# terraco_verde_pcb_impressa.net
KiCad netlist of a schematic drawn in EAGLE
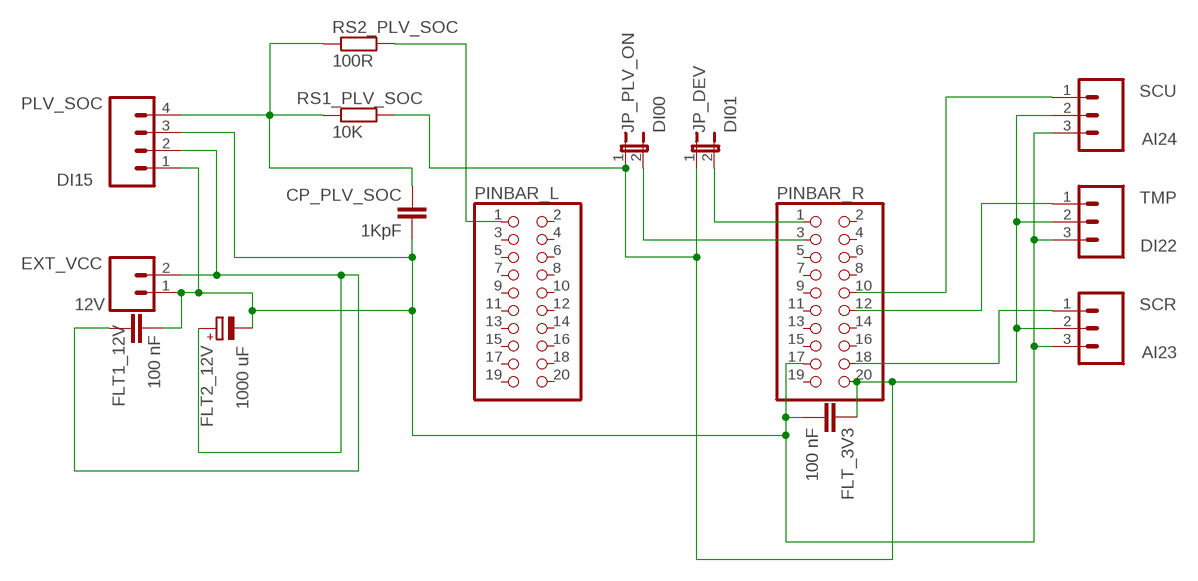
[diagram p0: schematic, sheet 1]

(export (version "E")
  (design (tool "Eeschema 10.0.6"))
  (components
    (comp (ref "CP_PLV_SOC")
      (value "1KpF")
      (footprint "eagle-import:C025-024X044")
      (libsource (lib "eagle-import") (part "C-EU025-024X044"))
    )
    (comp (ref "EXT_VCC")
      (value "12V")
      (footprint "eagle-import:02P")
      (libsource (lib "eagle-import") (part "M02"))
    )
    (comp (ref "FLT1_12V")
      (value "100 nF")
      (footprint "eagle-import:C025-024X044")
      (libsource (lib "eagle-import") (part "C-EU025-024X044"))
    )
    (comp (ref "FLT2_12V")
      (value "1000 uF")
      (footprint "eagle-import:E5-5")
      (libsource (lib "eagle-import") (part "CPOL-EUE5-5"))
    )
    (comp (ref "FLT_3V3")
      (value "100 nF")
      (footprint "eagle-import:C025-024X044")
      (libsource (lib "eagle-import") (part "C-EU025-024X044"))
    )
    (comp (ref "JP_DEV")
      (value "DI01")
      (footprint "eagle-import:JP1")
      (libsource (lib "eagle-import") (part "JP1E"))
    )
    (comp (ref "JP_PLV_ON")
      (value "DI00")
      (footprint "eagle-import:JP1")
      (libsource (lib "eagle-import") (part "JP1E"))
    )
    (comp (ref "PINBAR_L")
      (value "0")
      (footprint "eagle-import:2X10")
      (libsource (lib "eagle-import") (part "PINHD-2X10"))
    )
    (comp (ref "PINBAR_R")
      (value "1")
      (footprint "eagle-import:2X10")
      (libsource (lib "eagle-import") (part "PINHD-2X10"))
    )
    (comp (ref "PLV_SOC")
      (value "DI15")
      (footprint "eagle-import:04P")
      (libsource (lib "eagle-import") (part "M04"))
    )
    (comp (ref "RS1_PLV_SOC")
      (value "10K")
      (footprint "eagle-import:0207_7")
      (libsource (lib "eagle-import") (part "R-EU_0207/7"))
    )
    (comp (ref "RS2_PLV_SOC")
      (value "100R")
      (footprint "eagle-import:0207_7")
      (libsource (lib "eagle-import") (part "R-EU_0207/7"))
    )
    (comp (ref "SCR")
      (value "AI23")
      (footprint "eagle-import:03P")
      (libsource (lib "eagle-import") (part "M03"))
    )
    (comp (ref "SCU")
      (value "AI24")
      (footprint "eagle-import:03P")
      (libsource (lib "eagle-import") (part "M03"))
    )
    (comp (ref "TMP")
      (value "DI22")
      (footprint "eagle-import:03P")
      (libsource (lib "eagle-import") (part "M03"))
    )
  )
  (nets
    (net (code "1") (name "Net-(CP_PLV_SOC-Pad1)") (class "Default")
      (node (ref "CP_PLV_SOC") (pin "1") (pinfunction "1_1") (pintype "passive"))
      (node (ref "EXT_VCC") (pin "1") (pinfunction "1_1") (pintype "passive"))
      (node (ref "FLT1_12V") (pin "2") (pinfunction "2_2") (pintype "passive"))
      (node (ref "FLT2_12V") (pin "-") (pinfunction "-_-") (pintype "passive"))
      (node (ref "FLT_3V3") (pin "2") (pinfunction "2_2") (pintype "passive"))
      (node (ref "PINBAR_R") (pin "17") (pinfunction "17_17") (pintype "passive"))
      (node (ref "PLV_SOC") (pin "1") (pinfunction "1_1") (pintype "passive"))
      (node (ref "PLV_SOC") (pin "3") (pinfunction "3_3") (pintype "passive"))
      (node (ref "SCR") (pin "3") (pinfunction "3_3") (pintype "passive"))
      (node (ref "SCU") (pin "3") (pinfunction "3_3") (pintype "passive"))
      (node (ref "TMP") (pin "3") (pinfunction "3_3") (pintype "passive"))
    )
    (net (code "2") (name "Net-(CP_PLV_SOC-Pad2)") (class "Default")
      (node (ref "CP_PLV_SOC") (pin "2") (pinfunction "2_2") (pintype "passive"))
      (node (ref "PLV_SOC") (pin "4") (pinfunction "4_4") (pintype "passive"))
      (node (ref "RS1_PLV_SOC") (pin "1") (pinfunction "1_1") (pintype "passive"))
      (node (ref "RS2_PLV_SOC") (pin "1") (pinfunction "1_1") (pintype "passive"))
    )
    (net (code "3") (name "Net-(EXT_VCC-Pad2)") (class "Default")
      (node (ref "EXT_VCC") (pin "2") (pinfunction "2_2") (pintype "passive"))
      (node (ref "FLT1_12V") (pin "1") (pinfunction "1_1") (pintype "passive"))
      (node (ref "FLT2_12V") (pin "+") (pinfunction "+_+") (pintype "passive"))
      (node (ref "PLV_SOC") (pin "2") (pinfunction "2_2") (pintype "passive"))
    )
    (net (code "4") (name "Net-(FLT_3V3-Pad1)") (class "Default")
      (node (ref "FLT_3V3") (pin "1") (pinfunction "1_1") (pintype "passive"))
      (node (ref "JP_DEV") (pin "1") (pinfunction "1_1") (pintype "passive"))
      (node (ref "JP_PLV_ON") (pin "1") (pinfunction "1_1") (pintype "passive"))
      (node (ref "PINBAR_R") (pin "20") (pinfunction "20_20") (pintype "passive"))
      (node (ref "RS1_PLV_SOC") (pin "2") (pinfunction "2_2") (pintype "passive"))
      (node (ref "SCR") (pin "2") (pinfunction "2_2") (pintype "passive"))
      (node (ref "SCU") (pin "2") (pinfunction "2_2") (pintype "passive"))
      (node (ref "TMP") (pin "2") (pinfunction "2_2") (pintype "passive"))
    )
    (net (code "5") (name "Net-(JP_DEV-Pad2)") (class "Default")
      (node (ref "JP_DEV") (pin "2") (pinfunction "2_2") (pintype "passive"))
      (node (ref "PINBAR_R") (pin "1") (pinfunction "1_1") (pintype "passive"))
    )
    (net (code "6") (name "Net-(JP_PLV_ON-Pad2)") (class "Default")
      (node (ref "JP_PLV_ON") (pin "2") (pinfunction "2_2") (pintype "passive"))
      (node (ref "PINBAR_R") (pin "3") (pinfunction "3_3") (pintype "passive"))
    )
    (net (code "7") (name "Net-(PINBAR_L-Pad1)") (class "Default")
      (node (ref "PINBAR_L") (pin "1") (pinfunction "1_1") (pintype "passive"))
      (node (ref "RS2_PLV_SOC") (pin "2") (pinfunction "2_2") (pintype "passive"))
    )
    (net (code "8") (name "Net-(PINBAR_R-Pad10)") (class "Default")
      (node (ref "PINBAR_R") (pin "10") (pinfunction "10_10") (pintype "passive"))
      (node (ref "SCU") (pin "1") (pinfunction "1_1") (pintype "passive"))
    )
    (net (code "9") (name "Net-(PINBAR_R-Pad12)") (class "Default")
      (node (ref "PINBAR_R") (pin "12") (pinfunction "12_12") (pintype "passive"))
      (node (ref "TMP") (pin "1") (pinfunction "1_1") (pintype "passive"))
    )
    (net (code "10") (name "Net-(PINBAR_R-Pad18)") (class "Default")
      (node (ref "PINBAR_R") (pin "18") (pinfunction "18_18") (pintype "passive"))
      (node (ref "SCR") (pin "1") (pinfunction "1_1") (pintype "passive"))
    )
    (net (code "11") (name "unconnected-(PINBAR_L-Pad2)") (class "Default")
      (node (ref "PINBAR_L") (pin "2") (pinfunction "2_2") (pintype "passive"))
    )
    (net (code "12") (name "unconnected-(PINBAR_L-Pad3)") (class "Default")
      (node (ref "PINBAR_L") (pin "3") (pinfunction "3_3") (pintype "passive"))
    )
    (net (code "13") (name "unconnected-(PINBAR_L-Pad4)") (class "Default")
      (node (ref "PINBAR_L") (pin "4") (pinfunction "4_4") (pintype "passive"))
    )
    (net (code "14") (name "unconnected-(PINBAR_L-Pad5)") (class "Default")
      (node (ref "PINBAR_L") (pin "5") (pinfunction "5_5") (pintype "passive"))
    )
    (net (code "15") (name "unconnected-(PINBAR_L-Pad6)") (class "Default")
      (node (ref "PINBAR_L") (pin "6") (pinfunction "6_6") (pintype "passive"))
    )
    (net (code "16") (name "unconnected-(PINBAR_L-Pad7)") (class "Default")
      (node (ref "PINBAR_L") (pin "7") (pinfunction "7_7") (pintype "passive"))
    )
    (net (code "17") (name "unconnected-(PINBAR_L-Pad8)") (class "Default")
      (node (ref "PINBAR_L") (pin "8") (pinfunction "8_8") (pintype "passive"))
    )
    (net (code "18") (name "unconnected-(PINBAR_L-Pad9)") (class "Default")
      (node (ref "PINBAR_L") (pin "9") (pinfunction "9_9") (pintype "passive"))
    )
    (net (code "19") (name "unconnected-(PINBAR_L-Pad10)") (class "Default")
      (node (ref "PINBAR_L") (pin "10") (pinfunction "10_10") (pintype "passive"))
    )
    (net (code "20") (name "unconnected-(PINBAR_L-Pad11)") (class "Default")
      (node (ref "PINBAR_L") (pin "11") (pinfunction "11_11") (pintype "passive"))
    )
    (net (code "21") (name "unconnected-(PINBAR_L-Pad12)") (class "Default")
      (node (ref "PINBAR_L") (pin "12") (pinfunction "12_12") (pintype "passive"))
    )
    (net (code "22") (name "unconnected-(PINBAR_L-Pad13)") (class "Default")
      (node (ref "PINBAR_L") (pin "13") (pinfunction "13_13") (pintype "passive"))
    )
    (net (code "23") (name "unconnected-(PINBAR_L-Pad14)") (class "Default")
      (node (ref "PINBAR_L") (pin "14") (pinfunction "14_14") (pintype "passive"))
    )
    (net (code "24") (name "unconnected-(PINBAR_L-Pad15)") (class "Default")
      (node (ref "PINBAR_L") (pin "15") (pinfunction "15_15") (pintype "passive"))
    )
    (net (code "25") (name "unconnected-(PINBAR_L-Pad16)") (class "Default")
      (node (ref "PINBAR_L") (pin "16") (pinfunction "16_16") (pintype "passive"))
    )
    (net (code "26") (name "unconnected-(PINBAR_L-Pad17)") (class "Default")
      (node (ref "PINBAR_L") (pin "17") (pinfunction "17_17") (pintype "passive"))
    )
    (net (code "27") (name "unconnected-(PINBAR_L-Pad18)") (class "Default")
      (node (ref "PINBAR_L") (pin "18") (pinfunction "18_18") (pintype "passive"))
    )
    (net (code "28") (name "unconnected-(PINBAR_L-Pad19)") (class "Default")
      (node (ref "PINBAR_L") (pin "19") (pinfunction "19_19") (pintype "passive"))
    )
    (net (code "29") (name "unconnected-(PINBAR_L-Pad20)") (class "Default")
      (node (ref "PINBAR_L") (pin "20") (pinfunction "20_20") (pintype "passive"))
    )
    (net (code "30") (name "unconnected-(PINBAR_R-Pad2)") (class "Default")
      (node (ref "PINBAR_R") (pin "2") (pinfunction "2_2") (pintype "passive"))
    )
    (net (code "31") (name "unconnected-(PINBAR_R-Pad4)") (class "Default")
      (node (ref "PINBAR_R") (pin "4") (pinfunction "4_4") (pintype "passive"))
    )
    (net (code "32") (name "unconnected-(PINBAR_R-Pad5)") (class "Default")
      (node (ref "PINBAR_R") (pin "5") (pinfunction "5_5") (pintype "passive"))
    )
    (net (code "33") (name "unconnected-(PINBAR_R-Pad6)") (class "Default")
      (node (ref "PINBAR_R") (pin "6") (pinfunction "6_6") (pintype "passive"))
    )
    (net (code "34") (name "unconnected-(PINBAR_R-Pad7)") (class "Default")
      (node (ref "PINBAR_R") (pin "7") (pinfunction "7_7") (pintype "passive"))
    )
    (net (code "35") (name "unconnected-(PINBAR_R-Pad8)") (class "Default")
      (node (ref "PINBAR_R") (pin "8") (pinfunction "8_8") (pintype "passive"))
    )
    (net (code "36") (name "unconnected-(PINBAR_R-Pad9)") (class "Default")
      (node (ref "PINBAR_R") (pin "9") (pinfunction "9_9") (pintype "passive"))
    )
    (net (code "37") (name "unconnected-(PINBAR_R-Pad11)") (class "Default")
      (node (ref "PINBAR_R") (pin "11") (pinfunction "11_11") (pintype "passive"))
    )
    (net (code "38") (name "unconnected-(PINBAR_R-Pad13)") (class "Default")
      (node (ref "PINBAR_R") (pin "13") (pinfunction "13_13") (pintype "passive"))
    )
    (net (code "39") (name "unconnected-(PINBAR_R-Pad14)") (class "Default")
      (node (ref "PINBAR_R") (pin "14") (pinfunction "14_14") (pintype "passive"))
    )
    (net (code "40") (name "unconnected-(PINBAR_R-Pad15)") (class "Default")
      (node (ref "PINBAR_R") (pin "15") (pinfunction "15_15") (pintype "passive"))
    )
    (net (code "41") (name "unconnected-(PINBAR_R-Pad16)") (class "Default")
      (node (ref "PINBAR_R") (pin "16") (pinfunction "16_16") (pintype "passive"))
    )
    (net (code "42") (name "unconnected-(PINBAR_R-Pad19)") (class "Default")
      (node (ref "PINBAR_R") (pin "19") (pinfunction "19_19") (pintype "passive"))
    )
  )
)
